# pizero_w1.net
KiCad netlist of a schematic drawn in EAGLE
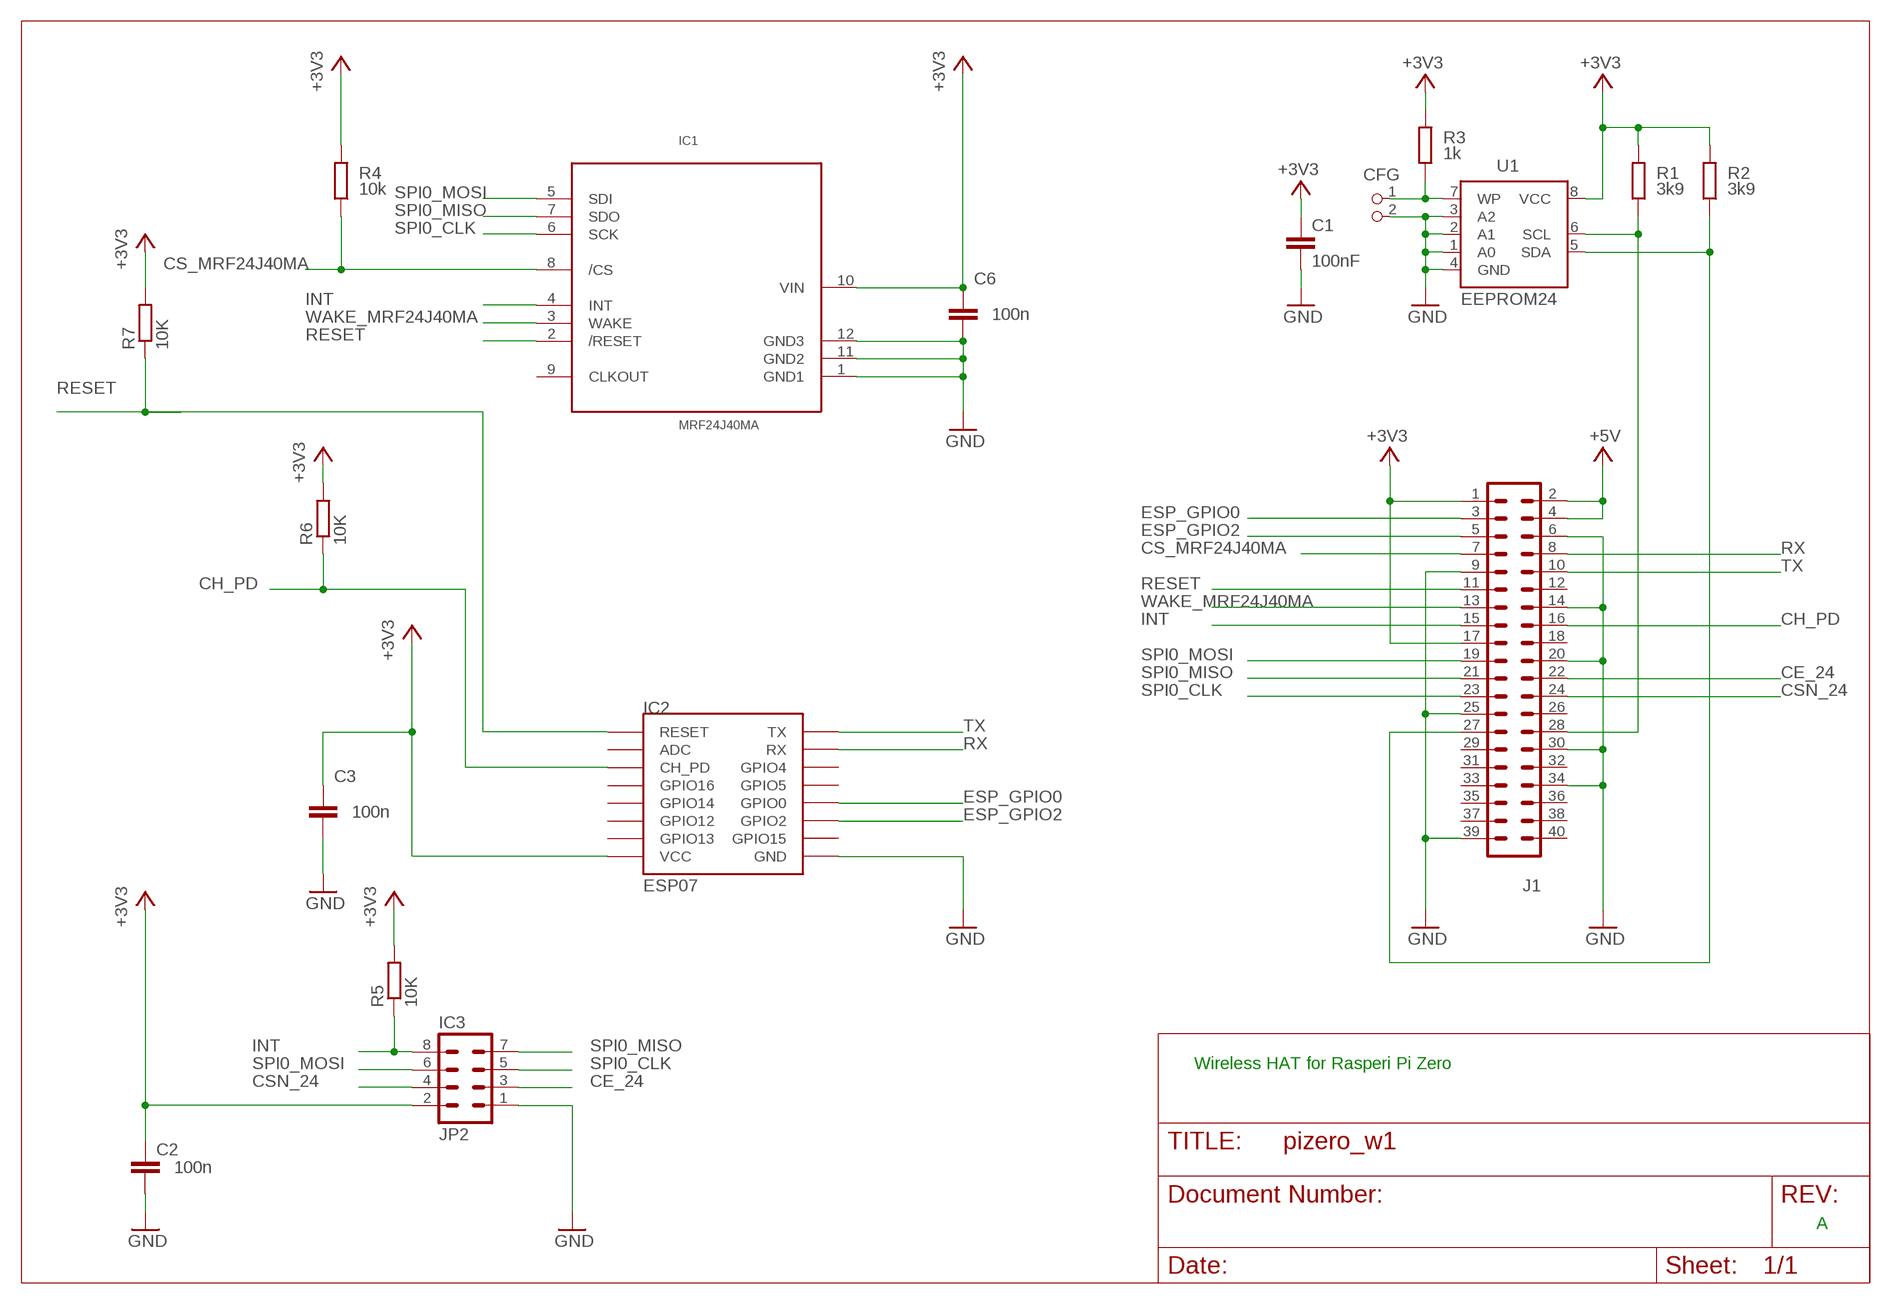
[diagram p0: schematic, sheet 1]

(export (version "E")
  (design (tool "Eeschema 10.0.6"))
  (components
    (comp (ref "C1")
      (value "100nF")
      (footprint "eagle-import:C0805K")
      (libsource (lib "eagle-import") (part "resistor_C-EUC0805K"))
    )
    (comp (ref "C2")
      (value "100n")
      (footprint "eagle-import:C0805")
      (libsource (lib "eagle-import") (part "C-EUC0805"))
    )
    (comp (ref "C3")
      (value "100n")
      (footprint "eagle-import:C0805")
      (libsource (lib "eagle-import") (part "C-EUC0805"))
    )
    (comp (ref "C6")
      (value "100n")
      (footprint "eagle-import:C0805")
      (libsource (lib "eagle-import") (part "C-EUC0805"))
    )
    (comp (ref "CFG")
      (value "PIN2_100")
      (footprint "eagle-import:PIN_W_2")
      (libsource (lib "eagle-import") (part "PIN2_100"))
    )
    (comp (ref "IC1")
      (value "MRF24J40MA")
      (footprint "eagle-import:MRF24J40MA")
      (libsource (lib "eagle-import") (part "MRF24J40MA"))
    )
    (comp (ref "IC2")
      (value "ESP07")
      (footprint "eagle-import:ESP12")
      (libsource (lib "eagle-import") (part "ESP12"))
    )
    (comp (ref "IC3")
      (value "JP2")
      (footprint "eagle-import:MA04-2")
      (libsource (lib "eagle-import") (part "MA04-2"))
    )
    (comp (ref "J1")
      (value "PIZERO_THROUGH_HOLE")
      (footprint "eagle-import:PIZERO_THOUGH_HOLE")
      (libsource (lib "eagle-import") (part "PIZERO_THROUGH_HOLE"))
    )
    (comp (ref "R1")
      (value "3k9")
      (footprint "eagle-import:M0805")
      (fields (field (name "TOLERANCE") "5%"))
      (libsource (lib "eagle-import") (part "resistor_R-EU_M0805"))
    )
    (comp (ref "R2")
      (value "3k9")
      (footprint "eagle-import:M0805")
      (fields (field (name "TOLERANCE") "5%"))
      (libsource (lib "eagle-import") (part "resistor_R-EU_M0805"))
    )
    (comp (ref "R3")
      (value "1k")
      (footprint "eagle-import:M0805")
      (fields (field (name "TOLERANCE") "5%"))
      (libsource (lib "eagle-import") (part "resistor_R-EU_M0805"))
    )
    (comp (ref "R4")
      (value "10k")
      (footprint "eagle-import:M0805")
      (fields (field (name "TOLERANCE") "5%"))
      (libsource (lib "eagle-import") (part "resistor_R-EU_M0805"))
    )
    (comp (ref "R5")
      (value "10K")
      (footprint "eagle-import:R0805")
      (libsource (lib "eagle-import") (part "R-EU_R0805"))
    )
    (comp (ref "R6")
      (value "10K")
      (footprint "eagle-import:R0805")
      (libsource (lib "eagle-import") (part "R-EU_R0805"))
    )
    (comp (ref "R7")
      (value "10K")
      (footprint "eagle-import:R0805")
      (libsource (lib "eagle-import") (part "R-EU_R0805"))
    )
    (comp (ref "U1")
      (value "EEPROM24")
      (footprint "eagle-import:SOIC8")
      (libsource (lib "eagle-import") (part "EEPROM24"))
    )
  )
  (nets
    (net (code "1") (name "+3V3") (class "Default")
      (node (ref "C1") (pin "1") (pinfunction "1_1") (pintype "passive"))
      (node (ref "C2") (pin "1") (pinfunction "1_1") (pintype "passive"))
      (node (ref "C3") (pin "1") (pinfunction "1_1") (pintype "passive"))
      (node (ref "C6") (pin "1") (pinfunction "1_1") (pintype "passive"))
      (node (ref "IC1") (pin "10") (pinfunction "VIN_10") (pintype "power_in"))
      (node (ref "IC2") (pin "VCC") (pinfunction "VCC_VCC") (pintype "bidirectional"))
      (node (ref "IC3") (pin "2") (pinfunction "2_2") (pintype "passive"))
      (node (ref "J1") (pin "1") (pinfunction "1_1") (pintype "passive"))
      (node (ref "J1") (pin "17") (pinfunction "17_17") (pintype "passive"))
      (node (ref "R1") (pin "2") (pinfunction "2_2") (pintype "passive"))
      (node (ref "R2") (pin "2") (pinfunction "2_2") (pintype "passive"))
      (node (ref "R3") (pin "2") (pinfunction "2_2") (pintype "passive"))
      (node (ref "R4") (pin "2") (pinfunction "2_2") (pintype "passive"))
      (node (ref "R5") (pin "2") (pinfunction "2_2") (pintype "passive"))
      (node (ref "R6") (pin "2") (pinfunction "2_2") (pintype "passive"))
      (node (ref "R7") (pin "2") (pinfunction "2_2") (pintype "passive"))
      (node (ref "U1") (pin "8") (pinfunction "VCC_8") (pintype "power_in"))
    )
    (net (code "2") (name "+5V") (class "Default")
      (node (ref "J1") (pin "2") (pinfunction "2_2") (pintype "passive"))
      (node (ref "J1") (pin "4") (pinfunction "4_4") (pintype "passive"))
    )
    (net (code "3") (name "/CE_24") (class "Default")
      (node (ref "IC3") (pin "3") (pinfunction "3_3") (pintype "passive"))
      (node (ref "J1") (pin "22") (pinfunction "22_22") (pintype "passive"))
    )
    (net (code "4") (name "/CH_PD") (class "Default")
      (node (ref "IC2") (pin "CH_PD") (pinfunction "CH_PD_CH_PD") (pintype "bidirectional"))
      (node (ref "J1") (pin "16") (pinfunction "16_16") (pintype "passive"))
      (node (ref "R6") (pin "1") (pinfunction "1_1") (pintype "passive"))
    )
    (net (code "5") (name "/CSN_24") (class "Default")
      (node (ref "IC3") (pin "4") (pinfunction "4_4") (pintype "passive"))
      (node (ref "J1") (pin "24") (pinfunction "24_24") (pintype "passive"))
    )
    (net (code "6") (name "/CS_MRF24J40MA") (class "Default")
      (node (ref "IC1") (pin "8") (pinfunction "/CS_8") (pintype "bidirectional"))
      (node (ref "J1") (pin "7") (pinfunction "7_7") (pintype "passive"))
      (node (ref "R4") (pin "1") (pinfunction "1_1") (pintype "passive"))
    )
    (net (code "7") (name "/ESP_GPIO0") (class "Default")
      (node (ref "IC2") (pin "GPIO0") (pinfunction "GPIO0_GPIO0") (pintype "bidirectional"))
      (node (ref "J1") (pin "3") (pinfunction "3_3") (pintype "passive"))
    )
    (net (code "8") (name "/ESP_GPIO2") (class "Default")
      (node (ref "IC2") (pin "GPIO2") (pinfunction "GPIO2_GPIO2") (pintype "bidirectional"))
      (node (ref "J1") (pin "5") (pinfunction "5_5") (pintype "passive"))
    )
    (net (code "9") (name "/INT") (class "Default")
      (node (ref "IC1") (pin "4") (pinfunction "INT_4") (pintype "bidirectional"))
      (node (ref "IC3") (pin "8") (pinfunction "8_8") (pintype "passive"))
      (node (ref "J1") (pin "15") (pinfunction "15_15") (pintype "passive"))
      (node (ref "R5") (pin "1") (pinfunction "1_1") (pintype "passive"))
    )
    (net (code "10") (name "/RESET") (class "Default")
      (node (ref "IC1") (pin "2") (pinfunction "/RESET_2") (pintype "bidirectional"))
      (node (ref "IC2") (pin "RESET") (pinfunction "RESET_RESET") (pintype "bidirectional"))
      (node (ref "J1") (pin "11") (pinfunction "11_11") (pintype "passive"))
      (node (ref "R7") (pin "1") (pinfunction "1_1") (pintype "passive"))
    )
    (net (code "11") (name "/RX") (class "Default")
      (node (ref "IC2") (pin "RX") (pinfunction "RX_RX") (pintype "bidirectional"))
      (node (ref "J1") (pin "8") (pinfunction "8_8") (pintype "passive"))
    )
    (net (code "12") (name "/SPI0_CLK") (class "Default")
      (node (ref "IC1") (pin "6") (pinfunction "SCK_6") (pintype "bidirectional"))
      (node (ref "IC3") (pin "5") (pinfunction "5_5") (pintype "passive"))
      (node (ref "J1") (pin "23") (pinfunction "23_23") (pintype "passive"))
    )
    (net (code "13") (name "/SPI0_MISO") (class "Default")
      (node (ref "IC1") (pin "7") (pinfunction "SDO_7") (pintype "bidirectional"))
      (node (ref "IC3") (pin "7") (pinfunction "7_7") (pintype "passive"))
      (node (ref "J1") (pin "21") (pinfunction "21_21") (pintype "passive"))
    )
    (net (code "14") (name "/SPI0_MOSI") (class "Default")
      (node (ref "IC1") (pin "5") (pinfunction "SDI_5") (pintype "bidirectional"))
      (node (ref "IC3") (pin "6") (pinfunction "6_6") (pintype "passive"))
      (node (ref "J1") (pin "19") (pinfunction "19_19") (pintype "passive"))
    )
    (net (code "15") (name "/TX") (class "Default")
      (node (ref "IC2") (pin "TX") (pinfunction "TX_TX") (pintype "bidirectional"))
      (node (ref "J1") (pin "10") (pinfunction "10_10") (pintype "passive"))
    )
    (net (code "16") (name "/WAKE_MRF24J40MA") (class "Default")
      (node (ref "IC1") (pin "3") (pinfunction "WAKE_3") (pintype "bidirectional"))
      (node (ref "J1") (pin "13") (pinfunction "13_13") (pintype "passive"))
    )
    (net (code "17") (name "GND") (class "Default")
      (node (ref "C1") (pin "2") (pinfunction "2_2") (pintype "passive"))
      (node (ref "C2") (pin "2") (pinfunction "2_2") (pintype "passive"))
      (node (ref "C3") (pin "2") (pinfunction "2_2") (pintype "passive"))
      (node (ref "C6") (pin "2") (pinfunction "2_2") (pintype "passive"))
      (node (ref "CFG") (pin "2") (pinfunction "2_2") (pintype "passive"))
      (node (ref "IC1") (pin "1") (pinfunction "GND1_1") (pintype "power_in"))
      (node (ref "IC1") (pin "11") (pinfunction "GND2_11") (pintype "power_in"))
      (node (ref "IC1") (pin "12") (pinfunction "GND3_12") (pintype "power_in"))
      (node (ref "IC2") (pin "GND") (pinfunction "GND_GND") (pintype "bidirectional"))
      (node (ref "IC3") (pin "1") (pinfunction "1_1") (pintype "passive"))
      (node (ref "J1") (pin "14") (pinfunction "14_14") (pintype "passive"))
      (node (ref "J1") (pin "20") (pinfunction "20_20") (pintype "passive"))
      (node (ref "J1") (pin "25") (pinfunction "25_25") (pintype "passive"))
      (node (ref "J1") (pin "30") (pinfunction "30_30") (pintype "passive"))
      (node (ref "J1") (pin "34") (pinfunction "34_34") (pintype "passive"))
      (node (ref "J1") (pin "39") (pinfunction "39_39") (pintype "passive"))
      (node (ref "J1") (pin "6") (pinfunction "6_6") (pintype "passive"))
      (node (ref "J1") (pin "9") (pinfunction "9_9") (pintype "passive"))
      (node (ref "U1") (pin "1") (pinfunction "A0_1") (pintype "input"))
      (node (ref "U1") (pin "2") (pinfunction "A1_2") (pintype "input"))
      (node (ref "U1") (pin "3") (pinfunction "A2_3") (pintype "input"))
      (node (ref "U1") (pin "4") (pinfunction "GND_4") (pintype "power_in"))
    )
    (net (code "18") (name "Net-(U1-SCL)") (class "Default")
      (node (ref "J1") (pin "28") (pinfunction "28_28") (pintype "passive"))
      (node (ref "R1") (pin "1") (pinfunction "1_1") (pintype "passive"))
      (node (ref "U1") (pin "6") (pinfunction "SCL_6") (pintype "input"))
    )
    (net (code "19") (name "Net-(U1-SDA)") (class "Default")
      (node (ref "J1") (pin "27") (pinfunction "27_27") (pintype "passive"))
      (node (ref "R2") (pin "1") (pinfunction "1_1") (pintype "passive"))
      (node (ref "U1") (pin "5") (pinfunction "SDA_5") (pintype "bidirectional"))
    )
    (net (code "20") (name "Net-(U1-WP)") (class "Default")
      (node (ref "CFG") (pin "1") (pinfunction "1_1") (pintype "passive"))
      (node (ref "R3") (pin "1") (pinfunction "1_1") (pintype "passive"))
      (node (ref "U1") (pin "7") (pinfunction "WP_7") (pintype "input"))
    )
    (net (code "21") (name "unconnected-(IC1-CLKOUT-Pad9)") (class "Default")
      (node (ref "IC1") (pin "9") (pinfunction "CLKOUT_9") (pintype "output"))
    )
    (net (code "22") (name "unconnected-(IC2-PadADC)") (class "Default")
      (node (ref "IC2") (pin "ADC") (pinfunction "ADC_ADC") (pintype "bidirectional"))
    )
    (net (code "23") (name "unconnected-(IC2-PadGPIO4)") (class "Default")
      (node (ref "IC2") (pin "GPIO4") (pinfunction "GPIO4_GPIO4") (pintype "bidirectional"))
    )
    (net (code "24") (name "unconnected-(IC2-PadGPIO5)") (class "Default")
      (node (ref "IC2") (pin "GPIO5") (pinfunction "GPIO5_GPIO5") (pintype "bidirectional"))
    )
    (net (code "25") (name "unconnected-(IC2-PadGPIO12)") (class "Default")
      (node (ref "IC2") (pin "GPIO12") (pinfunction "GPIO12_GPIO12") (pintype "bidirectional"))
    )
    (net (code "26") (name "unconnected-(IC2-PadGPIO13)") (class "Default")
      (node (ref "IC2") (pin "GPIO13") (pinfunction "GPIO13_GPIO13") (pintype "bidirectional"))
    )
    (net (code "27") (name "unconnected-(IC2-PadGPIO14)") (class "Default")
      (node (ref "IC2") (pin "GPIO14") (pinfunction "GPIO14_GPIO14") (pintype "bidirectional"))
    )
    (net (code "28") (name "unconnected-(IC2-PadGPIO15)") (class "Default")
      (node (ref "IC2") (pin "GPIO15") (pinfunction "GPIO15_GPIO15") (pintype "bidirectional"))
    )
    (net (code "29") (name "unconnected-(IC2-PadGPIO16)") (class "Default")
      (node (ref "IC2") (pin "GPIO16") (pinfunction "GPIO16_GPIO16") (pintype "bidirectional"))
    )
    (net (code "30") (name "unconnected-(J1-Pad12)") (class "Default")
      (node (ref "J1") (pin "12") (pinfunction "12_12") (pintype "passive"))
    )
    (net (code "31") (name "unconnected-(J1-Pad18)") (class "Default")
      (node (ref "J1") (pin "18") (pinfunction "18_18") (pintype "passive"))
    )
    (net (code "32") (name "unconnected-(J1-Pad26)") (class "Default")
      (node (ref "J1") (pin "26") (pinfunction "26_26") (pintype "passive"))
    )
    (net (code "33") (name "unconnected-(J1-Pad29)") (class "Default")
      (node (ref "J1") (pin "29") (pinfunction "29_29") (pintype "passive"))
    )
    (net (code "34") (name "unconnected-(J1-Pad31)") (class "Default")
      (node (ref "J1") (pin "31") (pinfunction "31_31") (pintype "passive"))
    )
    (net (code "35") (name "unconnected-(J1-Pad32)") (class "Default")
      (node (ref "J1") (pin "32") (pinfunction "32_32") (pintype "passive"))
    )
    (net (code "36") (name "unconnected-(J1-Pad33)") (class "Default")
      (node (ref "J1") (pin "33") (pinfunction "33_33") (pintype "passive"))
    )
    (net (code "37") (name "unconnected-(J1-Pad35)") (class "Default")
      (node (ref "J1") (pin "35") (pinfunction "35_35") (pintype "passive"))
    )
    (net (code "38") (name "unconnected-(J1-Pad36)") (class "Default")
      (node (ref "J1") (pin "36") (pinfunction "36_36") (pintype "passive"))
    )
    (net (code "39") (name "unconnected-(J1-Pad37)") (class "Default")
      (node (ref "J1") (pin "37") (pinfunction "37_37") (pintype "passive"))
    )
    (net (code "40") (name "unconnected-(J1-Pad38)") (class "Default")
      (node (ref "J1") (pin "38") (pinfunction "38_38") (pintype "passive"))
    )
    (net (code "41") (name "unconnected-(J1-Pad40)") (class "Default")
      (node (ref "J1") (pin "40") (pinfunction "40_40") (pintype "passive"))
    )
  )
)
